# bmi270_modul.net
KiCad netlist of a schematic drawn in EasyEDA Pro
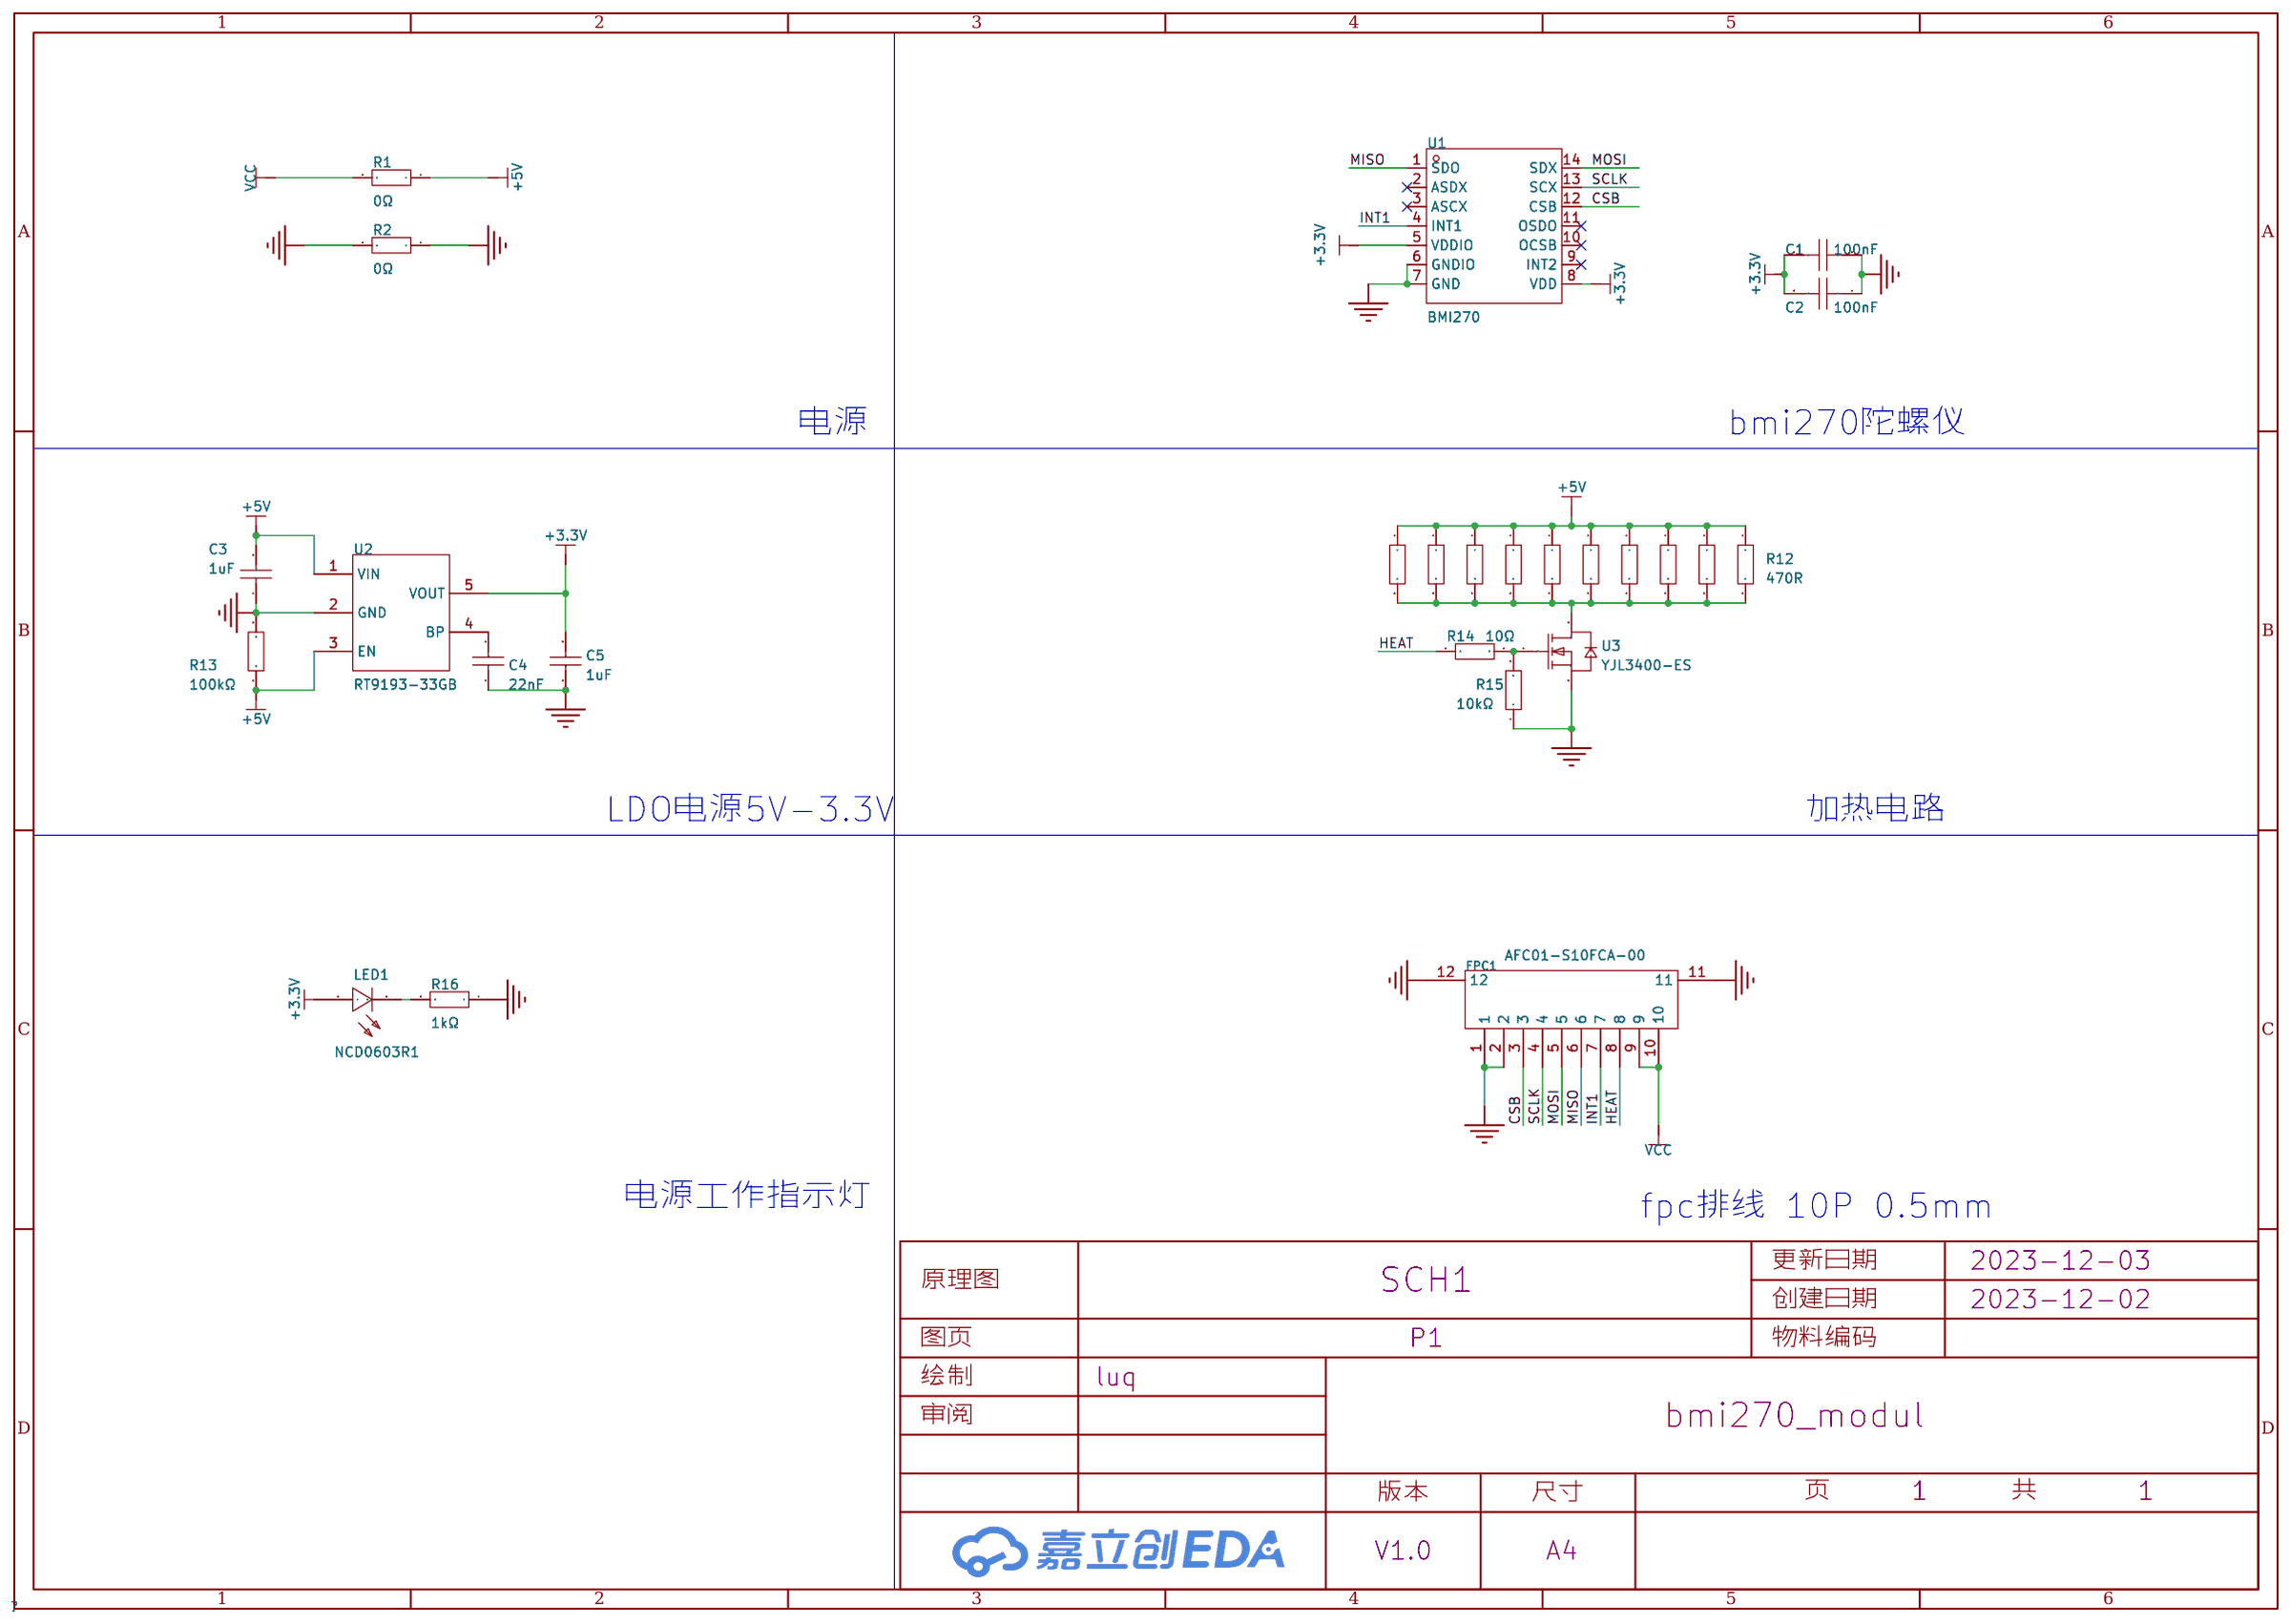
[diagram p0: schematic sheet]

(export (version "E")
  (design (tool "Eeschema 10.0.6"))
  (components
    (comp (ref "C1")
      (value "100nF")
      (footprint "easyedapro:C0402")
      (description "容值:100nF;精度:±10%;额定电压:50V;材质(温度系数):X7R;")
      (fields
        (field (name "Manufacturer Part") "GRM155R71H104KE14D")
        (field (name "Manufacturer") "muRata(村田)")
      )
      (libsource (lib "easyedapro") (part "GRM155R71H104KE14D"))
    )
    (comp (ref "C2")
      (value "100nF")
      (footprint "easyedapro:C0402")
      (description "容值:100nF;精度:±10%;额定电压:50V;材质(温度系数):X7R;")
      (fields
        (field (name "Manufacturer Part") "GRM155R71H104KE14D")
        (field (name "Manufacturer") "muRata(村田)")
      )
      (libsource (lib "easyedapro") (part "GRM155R71H104KE14D"))
    )
    (comp (ref "C3")
      (value "1uF")
      (footprint "easyedapro:C0402")
      (description "容值:1uF;精度:±10%;额定电压:10V;材质(温度系数):X5R;")
      (fields
        (field (name "Manufacturer Part") "CL05A105KP5NNNC")
        (field (name "Manufacturer") "SAMSUNG(三星)")
      )
      (libsource (lib "easyedapro") (part "CL05A105KP5NNNC"))
    )
    (comp (ref "C4")
      (value "22nF")
      (footprint "easyedapro:C0402")
      (description "容值:22nF;精度:±10%;额定电压:50V;材质(温度系数):X7R;")
      (fields (field (name "Manufacturer Part") "0402B223K500NT") (field (name "Manufacturer") "FH(风华)"))
      (libsource (lib "easyedapro") (part "0402B223K500NT"))
    )
    (comp (ref "C5")
      (value "1uF")
      (footprint "easyedapro:C0402")
      (description "容值:1uF;精度:±10%;额定电压:10V;材质(温度系数):X5R;")
      (fields
        (field (name "Manufacturer Part") "CL05A105KP5NNNC")
        (field (name "Manufacturer") "SAMSUNG(三星)")
      )
      (libsource (lib "easyedapro") (part "CL05A105KP5NNNC"))
    )
    (comp (ref "FPC1")
      (value "AFC01-S10FCA-00")
      (footprint "easyedapro:FPC-SMD_P0.5-10P_FGS-XJ-H2.0")
      (description "间距:0.5mm;触点数量:10P;锁定特性:翻盖式;安装类型:卧贴;触点类型:下接;")
      (fields (field (name "Manufacturer") "JS(钜硕电子)"))
      (libsource (lib "easyedapro") (part "AFC01-S10FCA-00"))
    )
    (comp (ref "LED1")
      (value "NCD0603R1")
      (footprint "easyedapro:LED0603-RD_RED")
      (description "发光颜色:红色;功率:65mW;透镜颜色:无色透明;主波长:615nm~630nm;发光强度:80mcd~220mcd;发光角度:130°;工作温度:-30°C~+85°C;")
      (fields (field (name "Manufacturer") "国星光电"))
      (libsource (lib "easyedapro") (part "FC-DA1608HRK-620D"))
    )
    (comp (ref "R1")
      (value "0Ω")
      (footprint "easyedapro:R0402")
      (description "电阻类型:厚膜电阻;阻值:100kΩ;精度:±1%;功率:62.5mW;")
      (fields (field (name "Manufacturer Part") "RC0402FR-07100KL") (field (name "Manufacturer") "YAGEO(国巨)"))
      (libsource (lib "easyedapro") (part "RC0402FR-07100KL"))
    )
    (comp (ref "R2")
      (value "0Ω")
      (footprint "easyedapro:R0402")
      (description "电阻类型:厚膜电阻;阻值:100kΩ;精度:±1%;功率:62.5mW;")
      (fields (field (name "Manufacturer Part") "RC0402FR-07100KL") (field (name "Manufacturer") "YAGEO(国巨)"))
      (libsource (lib "easyedapro") (part "RC0402FR-07100KL"))
    )
    (comp (ref "R3")
      (value "470R")
      (footprint "easyedapro:R0402")
      (description "电阻类型:厚膜电阻;阻值:100kΩ;精度:±1%;功率:62.5mW;")
      (fields (field (name "Manufacturer Part") "RC0402FR-07100KL") (field (name "Manufacturer") "YAGEO(国巨)"))
      (libsource (lib "easyedapro") (part "RC0402FR-07100KL"))
    )
    (comp (ref "R4")
      (value "470R")
      (footprint "easyedapro:R0402")
      (description "电阻类型:厚膜电阻;阻值:100kΩ;精度:±1%;功率:62.5mW;")
      (fields (field (name "Manufacturer Part") "RC0402FR-07100KL") (field (name "Manufacturer") "YAGEO(国巨)"))
      (libsource (lib "easyedapro") (part "RC0402FR-07100KL"))
    )
    (comp (ref "R5")
      (value "470R")
      (footprint "easyedapro:R0402")
      (description "电阻类型:厚膜电阻;阻值:100kΩ;精度:±1%;功率:62.5mW;")
      (fields (field (name "Manufacturer Part") "RC0402FR-07100KL") (field (name "Manufacturer") "YAGEO(国巨)"))
      (libsource (lib "easyedapro") (part "RC0402FR-07100KL"))
    )
    (comp (ref "R6")
      (value "470R")
      (footprint "easyedapro:R0402")
      (description "电阻类型:厚膜电阻;阻值:100kΩ;精度:±1%;功率:62.5mW;")
      (fields (field (name "Manufacturer Part") "RC0402FR-07100KL") (field (name "Manufacturer") "YAGEO(国巨)"))
      (libsource (lib "easyedapro") (part "RC0402FR-07100KL"))
    )
    (comp (ref "R7")
      (value "470R")
      (footprint "easyedapro:R0402")
      (description "电阻类型:厚膜电阻;阻值:100kΩ;精度:±1%;功率:62.5mW;")
      (fields (field (name "Manufacturer Part") "RC0402FR-07100KL") (field (name "Manufacturer") "YAGEO(国巨)"))
      (libsource (lib "easyedapro") (part "RC0402FR-07100KL"))
    )
    (comp (ref "R8")
      (value "470R")
      (footprint "easyedapro:R0402")
      (description "电阻类型:厚膜电阻;阻值:100kΩ;精度:±1%;功率:62.5mW;")
      (fields (field (name "Manufacturer Part") "RC0402FR-07100KL") (field (name "Manufacturer") "YAGEO(国巨)"))
      (libsource (lib "easyedapro") (part "RC0402FR-07100KL"))
    )
    (comp (ref "R9")
      (value "470R")
      (footprint "easyedapro:R0402")
      (description "电阻类型:厚膜电阻;阻值:100kΩ;精度:±1%;功率:62.5mW;")
      (fields (field (name "Manufacturer Part") "RC0402FR-07100KL") (field (name "Manufacturer") "YAGEO(国巨)"))
      (libsource (lib "easyedapro") (part "RC0402FR-07100KL"))
    )
    (comp (ref "R10")
      (value "470R")
      (footprint "easyedapro:R0402")
      (description "电阻类型:厚膜电阻;阻值:100kΩ;精度:±1%;功率:62.5mW;")
      (fields (field (name "Manufacturer Part") "RC0402FR-07100KL") (field (name "Manufacturer") "YAGEO(国巨)"))
      (libsource (lib "easyedapro") (part "RC0402FR-07100KL"))
    )
    (comp (ref "R11")
      (value "470R")
      (footprint "easyedapro:R0402")
      (description "电阻类型:厚膜电阻;阻值:100kΩ;精度:±1%;功率:62.5mW;")
      (fields (field (name "Manufacturer Part") "RC0402FR-07100KL") (field (name "Manufacturer") "YAGEO(国巨)"))
      (libsource (lib "easyedapro") (part "RC0402FR-07100KL"))
    )
    (comp (ref "R12")
      (value "470R")
      (footprint "easyedapro:R0402")
      (description "电阻类型:厚膜电阻;阻值:100kΩ;精度:±1%;功率:62.5mW;")
      (fields (field (name "Manufacturer Part") "RC0402FR-07100KL") (field (name "Manufacturer") "YAGEO(国巨)"))
      (libsource (lib "easyedapro") (part "RC0402FR-07100KL"))
    )
    (comp (ref "R13")
      (value "100kΩ")
      (footprint "easyedapro:R0402")
      (description "电阻类型:厚膜电阻;阻值:100kΩ;精度:±1%;功率:62.5mW;")
      (fields (field (name "Manufacturer Part") "RC0402FR-07100KL") (field (name "Manufacturer") "YAGEO(国巨)"))
      (libsource (lib "easyedapro") (part "RC0402FR-07100KL"))
    )
    (comp (ref "R14")
      (value "10Ω")
      (footprint "easyedapro:R0402")
      (description "电阻类型:厚膜电阻;阻值:100kΩ;精度:±1%;功率:62.5mW;")
      (fields (field (name "Manufacturer Part") "RC0402FR-07100KL") (field (name "Manufacturer") "YAGEO(国巨)"))
      (libsource (lib "easyedapro") (part "RC0402FR-07100KL"))
    )
    (comp (ref "R15")
      (value "10kΩ")
      (footprint "easyedapro:R0402")
      (description "电阻类型:厚膜电阻;阻值:100kΩ;精度:±1%;功率:62.5mW;")
      (fields (field (name "Manufacturer Part") "RC0402FR-07100KL") (field (name "Manufacturer") "YAGEO(国巨)"))
      (libsource (lib "easyedapro") (part "RC0402FR-07100KL"))
    )
    (comp (ref "R16")
      (value "1kΩ")
      (footprint "easyedapro:R0402")
      (description "电阻类型:厚膜电阻;阻值:100kΩ;精度:±1%;功率:62.5mW;")
      (fields (field (name "Manufacturer Part") "RC0402FR-07100KL") (field (name "Manufacturer") "YAGEO(国巨)"))
      (libsource (lib "easyedapro") (part "RC0402FR-07100KL"))
    )
    (comp (ref "U1")
      (value "BMI270")
      (footprint "easyedapro:LGA-14_L3.0-W2.5-P0.50-BR")
      (description "IMU-惯性测量单元")
      (fields (field (name "Manufacturer") "Bosch(博世)"))
      (libsource (lib "easyedapro") (part "BMI270"))
    )
    (comp (ref "U2")
      (value "RT9193-33GB")
      (footprint "easyedapro:SOT-23-5_L3.0-W1.7-P0.95-LS2.8-BL")
      (description "输出类型:固定;输出极性:正;输出通道数:1;最大输入电压:5.5V;输出电压:3.3V;压差:300mV@(300mA);输出电流:300mA;电源纹波抑制比(PSRR):70dB;")
      (fields (field (name "Manufacturer") "RICHTEK(立锜)"))
      (libsource (lib "easyedapro") (part "RT9193-33GB"))
    )
    (comp (ref "U3")
      (value "YJL3400-ES")
      (footprint "easyedapro:SOT-23-3_L2.9-W1.3-P1.90-LS2.4-BR")
      (description "类型:N沟道;漏源电压(Vdss):30V;连续漏极电流(Id):6A;功率(Pd):1.4W;导通电阻(RDS(on)@Vgs,Id):19mΩ@10V,6.0A;")
      (fields (field (name "Manufacturer") "ElecSuper(静芯微）"))
      (libsource (lib "easyedapro") (part "YJL3400-ES"))
    )
  )
  (nets
    (net (code "1") (name "+3.3V") (class "Default")
      (node (ref "C1") (pin "2") (pinfunction "2_2") (pintype "unspecified"))
      (node (ref "C2") (pin "2") (pinfunction "2_2") (pintype "unspecified"))
      (node (ref "C5") (pin "2") (pinfunction "2_2") (pintype "input"))
      (node (ref "LED1") (pin "2") (pinfunction "A_2") (pintype "input"))
      (node (ref "U1") (pin "5") (pinfunction "VDDIO_5") (pintype "input"))
      (node (ref "U1") (pin "8") (pinfunction "VDD_8") (pintype "input"))
      (node (ref "U2") (pin "5") (pinfunction "VOUT_5") (pintype "input"))
    )
    (net (code "2") (name "+5V") (class "Default")
      (node (ref "C3") (pin "2") (pinfunction "2_2") (pintype "input"))
      (node (ref "R1") (pin "1") (pinfunction "1_1") (pintype "input"))
      (node (ref "R10") (pin "1") (pinfunction "1_1") (pintype "input"))
      (node (ref "R11") (pin "1") (pinfunction "1_1") (pintype "input"))
      (node (ref "R12") (pin "1") (pinfunction "1_1") (pintype "input"))
      (node (ref "R13") (pin "1") (pinfunction "1_1") (pintype "input"))
      (node (ref "R3") (pin "1") (pinfunction "1_1") (pintype "input"))
      (node (ref "R4") (pin "1") (pinfunction "1_1") (pintype "input"))
      (node (ref "R5") (pin "1") (pinfunction "1_1") (pintype "input"))
      (node (ref "R6") (pin "1") (pinfunction "1_1") (pintype "input"))
      (node (ref "R7") (pin "1") (pinfunction "1_1") (pintype "input"))
      (node (ref "R8") (pin "1") (pinfunction "1_1") (pintype "input"))
      (node (ref "R9") (pin "1") (pinfunction "1_1") (pintype "input"))
      (node (ref "U2") (pin "1") (pinfunction "VIN_1") (pintype "input"))
      (node (ref "U2") (pin "3") (pinfunction "EN_3") (pintype "input"))
    )
    (net (code "3") (name "/CSB") (class "Default")
      (node (ref "FPC1") (pin "3") (pinfunction "3_3") (pintype "input"))
      (node (ref "U1") (pin "12") (pinfunction "CSB_12") (pintype "input"))
    )
    (net (code "4") (name "/HEAT") (class "Default")
      (node (ref "FPC1") (pin "8") (pinfunction "8_8") (pintype "input"))
      (node (ref "R14") (pin "2") (pinfunction "2_2") (pintype "input"))
    )
    (net (code "5") (name "/INT1") (class "Default")
      (node (ref "FPC1") (pin "7") (pinfunction "7_7") (pintype "input"))
      (node (ref "U1") (pin "4") (pinfunction "INT1_4") (pintype "input"))
    )
    (net (code "6") (name "/MISO") (class "Default")
      (node (ref "FPC1") (pin "6") (pinfunction "6_6") (pintype "input"))
      (node (ref "U1") (pin "1") (pinfunction "SDO_1") (pintype "input"))
    )
    (net (code "7") (name "/MOSI") (class "Default")
      (node (ref "FPC1") (pin "5") (pinfunction "5_5") (pintype "input"))
      (node (ref "U1") (pin "14") (pinfunction "SDX_14") (pintype "input"))
    )
    (net (code "8") (name "/SCLK") (class "Default")
      (node (ref "FPC1") (pin "4") (pinfunction "4_4") (pintype "input"))
      (node (ref "U1") (pin "13") (pinfunction "SCX_13") (pintype "input"))
    )
    (net (code "9") (name "GND") (class "Default")
      (node (ref "C1") (pin "1") (pinfunction "1_1") (pintype "unspecified"))
      (node (ref "C2") (pin "1") (pinfunction "1_1") (pintype "unspecified"))
      (node (ref "C3") (pin "1") (pinfunction "1_1") (pintype "input"))
      (node (ref "C4") (pin "1") (pinfunction "1_1") (pintype "input"))
      (node (ref "C5") (pin "1") (pinfunction "1_1") (pintype "input"))
      (node (ref "FPC1") (pin "11") (pinfunction "11_11") (pintype "input"))
      (node (ref "FPC1") (pin "12") (pinfunction "12_12") (pintype "input"))
      (node (ref "R13") (pin "2") (pinfunction "2_2") (pintype "input"))
      (node (ref "R15") (pin "1") (pinfunction "1_1") (pintype "input"))
      (node (ref "R16") (pin "1") (pinfunction "1_1") (pintype "input"))
      (node (ref "R2") (pin "1") (pinfunction "1_1") (pintype "input"))
      (node (ref "U1") (pin "6") (pinfunction "GNDIO_6") (pintype "input"))
      (node (ref "U1") (pin "7") (pinfunction "GND_7") (pintype "input"))
      (node (ref "U2") (pin "2") (pinfunction "GND_2") (pintype "input"))
      (node (ref "U3") (pin "2") (pinfunction "S_2") (pintype "unspecified"))
    )
    (net (code "10") (name "Net-(LED1-K)") (class "Default")
      (node (ref "LED1") (pin "1") (pinfunction "K_1") (pintype "input"))
      (node (ref "R16") (pin "2") (pinfunction "2_2") (pintype "input"))
    )
    (net (code "11") (name "Net-(U2-BP)") (class "Default")
      (node (ref "C4") (pin "2") (pinfunction "2_2") (pintype "input"))
      (node (ref "U2") (pin "4") (pinfunction "BP_4") (pintype "input"))
    )
    (net (code "12") (name "Net-(U3-D)") (class "Default")
      (node (ref "R10") (pin "2") (pinfunction "2_2") (pintype "input"))
      (node (ref "R11") (pin "2") (pinfunction "2_2") (pintype "input"))
      (node (ref "R12") (pin "2") (pinfunction "2_2") (pintype "input"))
      (node (ref "R3") (pin "2") (pinfunction "2_2") (pintype "input"))
      (node (ref "R4") (pin "2") (pinfunction "2_2") (pintype "input"))
      (node (ref "R5") (pin "2") (pinfunction "2_2") (pintype "input"))
      (node (ref "R6") (pin "2") (pinfunction "2_2") (pintype "input"))
      (node (ref "R7") (pin "2") (pinfunction "2_2") (pintype "input"))
      (node (ref "R8") (pin "2") (pinfunction "2_2") (pintype "input"))
      (node (ref "R9") (pin "2") (pinfunction "2_2") (pintype "input"))
      (node (ref "U3") (pin "3") (pinfunction "D_3") (pintype "unspecified"))
    )
    (net (code "13") (name "Net-(U3-G)") (class "Default")
      (node (ref "R14") (pin "1") (pinfunction "1_1") (pintype "input"))
      (node (ref "R15") (pin "2") (pinfunction "2_2") (pintype "input"))
      (node (ref "U3") (pin "1") (pinfunction "G_1") (pintype "unspecified"))
    )
    (net (code "14") (name "PGND") (class "Default")
      (node (ref "FPC1") (pin "1") (pinfunction "1_1") (pintype "input"))
      (node (ref "FPC1") (pin "2") (pinfunction "2_2") (pintype "input"))
      (node (ref "R2") (pin "2") (pinfunction "2_2") (pintype "input"))
    )
    (net (code "15") (name "VCC") (class "Default")
      (node (ref "FPC1") (pin "10") (pinfunction "10_10") (pintype "input"))
      (node (ref "FPC1") (pin "9") (pinfunction "9_9") (pintype "input"))
      (node (ref "R1") (pin "2") (pinfunction "2_2") (pintype "input"))
    )
    (net (code "16") (name "unconnected-(U1-ASCX-Pad3)") (class "Default")
      (node (ref "U1") (pin "3") (pinfunction "ASCX_3") (pintype "input+no_connect"))
    )
    (net (code "17") (name "unconnected-(U1-ASDX-Pad2)") (class "Default")
      (node (ref "U1") (pin "2") (pinfunction "ASDX_2") (pintype "input+no_connect"))
    )
    (net (code "18") (name "unconnected-(U1-INT2-Pad9)") (class "Default")
      (node (ref "U1") (pin "9") (pinfunction "INT2_9") (pintype "input+no_connect"))
    )
    (net (code "19") (name "unconnected-(U1-OCSB-Pad10)") (class "Default")
      (node (ref "U1") (pin "10") (pinfunction "OCSB_10") (pintype "input+no_connect"))
    )
    (net (code "20") (name "unconnected-(U1-OSDO-Pad11)") (class "Default")
      (node (ref "U1") (pin "11") (pinfunction "OSDO_11") (pintype "input+no_connect"))
    )
  )
)
